# version_0_test.net
KiCad netlist of a schematic drawn in EAGLE
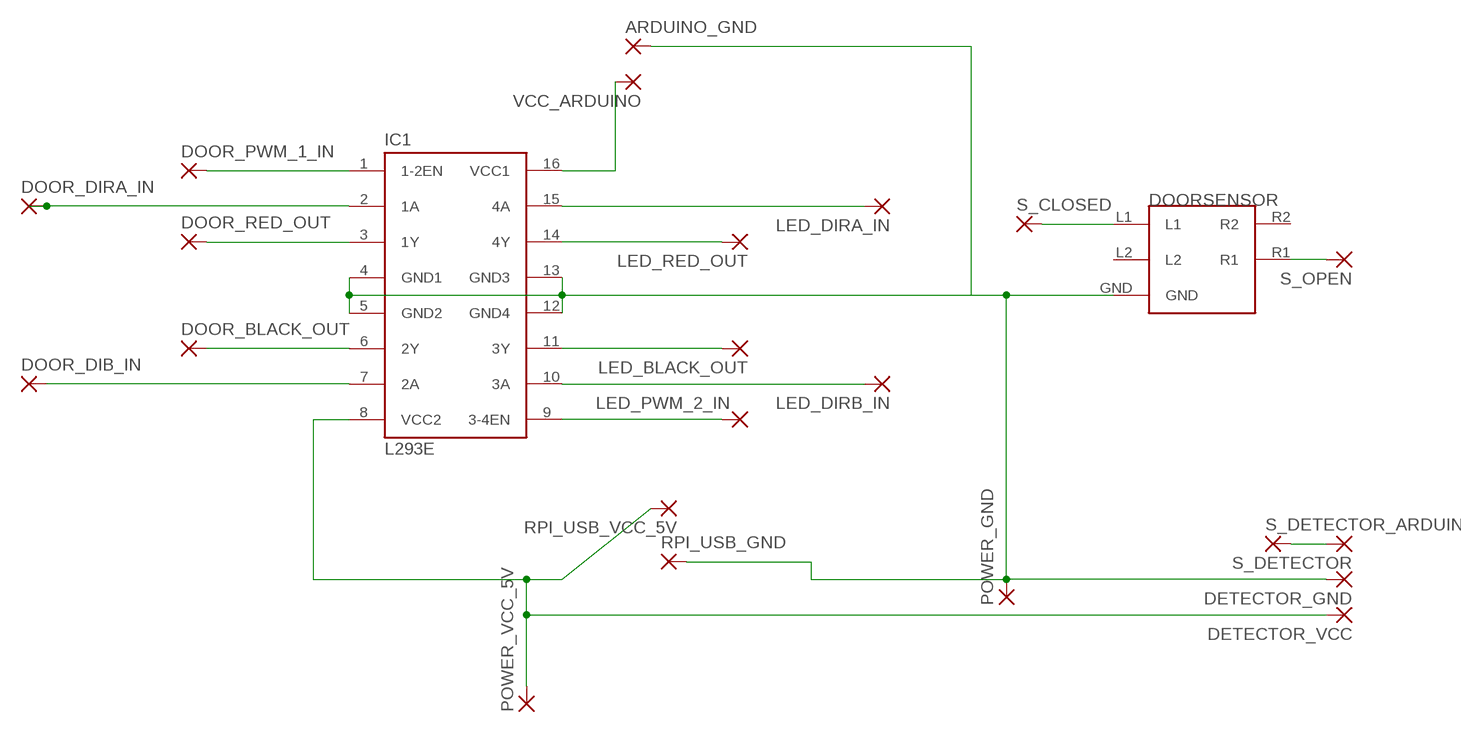
[diagram p0: schematic, sheet 1]

(export (version "E")
  (design (tool "Eeschema 10.0.6"))
  (components
    (comp (ref "ARDUINO_GND")
      (value "SMD5")
      (footprint "eagle-import:SMD2,54-5,08")
      (libsource (lib "eagle-import") (part "SMD5"))
    )
    (comp (ref "DETECTOR_GND")
      (value "SMD5")
      (footprint "eagle-import:SMD2,54-5,08")
      (libsource (lib "eagle-import") (part "SMD5"))
    )
    (comp (ref "DETECTOR_VCC")
      (value "SMD5")
      (footprint "eagle-import:SMD2,54-5,08")
      (libsource (lib "eagle-import") (part "SMD5"))
    )
    (comp (ref "DOORSENSOR")
      (value "DOORSENSOR")
      (footprint "eagle-import:DOORSENSOR")
      (libsource (lib "eagle-import") (part "DOORSENSOR"))
    )
    (comp (ref "DOOR_BLACK_OUT")
      (value "SMD5")
      (footprint "eagle-import:SMD2,54-5,08")
      (libsource (lib "eagle-import") (part "SMD5"))
    )
    (comp (ref "DOOR_DIB_IN")
      (value "SMD5")
      (footprint "eagle-import:SMD2,54-5,08")
      (libsource (lib "eagle-import") (part "SMD5"))
    )
    (comp (ref "DOOR_DIRA_IN")
      (value "SMD5")
      (footprint "eagle-import:SMD2,54-5,08")
      (libsource (lib "eagle-import") (part "SMD5"))
    )
    (comp (ref "DOOR_PWM_1_IN")
      (value "SMD5")
      (footprint "eagle-import:SMD2,54-5,08")
      (libsource (lib "eagle-import") (part "SMD5"))
    )
    (comp (ref "DOOR_RED_OUT")
      (value "SMD5")
      (footprint "eagle-import:SMD2,54-5,08")
      (libsource (lib "eagle-import") (part "SMD5"))
    )
    (comp (ref "IC1")
      (value "L293E")
      (footprint "eagle-import:DIL16")
      (fields (field (name "MF") "Arrow Electronics"))
      (libsource (lib "eagle-import") (part "L293E"))
    )
    (comp (ref "LED_BLACK_OUT")
      (value "SMD5")
      (footprint "eagle-import:SMD2,54-5,08")
      (libsource (lib "eagle-import") (part "SMD5"))
    )
    (comp (ref "LED_DIRA_IN")
      (value "SMD5")
      (footprint "eagle-import:SMD2,54-5,08")
      (libsource (lib "eagle-import") (part "SMD5"))
    )
    (comp (ref "LED_DIRB_IN")
      (value "SMD5")
      (footprint "eagle-import:SMD2,54-5,08")
      (libsource (lib "eagle-import") (part "SMD5"))
    )
    (comp (ref "LED_PWM_2_IN")
      (value "SMD5")
      (footprint "eagle-import:SMD2,54-5,08")
      (libsource (lib "eagle-import") (part "SMD5"))
    )
    (comp (ref "LED_RED_OUT")
      (value "SMD5")
      (footprint "eagle-import:SMD2,54-5,08")
      (libsource (lib "eagle-import") (part "SMD5"))
    )
    (comp (ref "POWER_GND")
      (value "SMD5")
      (footprint "eagle-import:SMD2,54-5,08")
      (libsource (lib "eagle-import") (part "SMD5"))
    )
    (comp (ref "POWER_VCC_5V")
      (value "SMD5")
      (footprint "eagle-import:SMD2,54-5,08")
      (libsource (lib "eagle-import") (part "SMD5"))
    )
    (comp (ref "RPI_USB_GND")
      (value "SMD5")
      (footprint "eagle-import:SMD2,54-5,08")
      (libsource (lib "eagle-import") (part "SMD5"))
    )
    (comp (ref "RPI_USB_VCC_5V")
      (value "SMD5")
      (footprint "eagle-import:SMD2,54-5,08")
      (libsource (lib "eagle-import") (part "SMD5"))
    )
    (comp (ref "S_CLOSED")
      (value "SMD5")
      (footprint "eagle-import:SMD2,54-5,08")
      (libsource (lib "eagle-import") (part "SMD5"))
    )
    (comp (ref "S_DETECTOR")
      (value "SMD5")
      (footprint "eagle-import:SMD2,54-5,08")
      (libsource (lib "eagle-import") (part "SMD5"))
    )
    (comp (ref "S_DETECTOR_ARDUINO")
      (value "SMD5")
      (footprint "eagle-import:SMD2,54-5,08")
      (libsource (lib "eagle-import") (part "SMD5"))
    )
    (comp (ref "S_OPEN")
      (value "SMD5")
      (footprint "eagle-import:SMD2,54-5,08")
      (libsource (lib "eagle-import") (part "SMD5"))
    )
    (comp (ref "VCC_ARDUINO")
      (value "SMD5")
      (footprint "eagle-import:SMD2,54-5,08")
      (libsource (lib "eagle-import") (part "SMD5"))
    )
  )
  (nets
    (net (code "1") (name "Net-(ARDUINO_GND-P)") (class "Default")
      (node (ref "ARDUINO_GND") (pin "1") (pinfunction "P_1") (pintype "passive"))
      (node (ref "DETECTOR_GND") (pin "1") (pinfunction "P_1") (pintype "passive"))
      (node (ref "DOORSENSOR") (pin "GND") (pinfunction "GND_GND") (pintype "bidirectional"))
      (node (ref "IC1") (pin "12") (pinfunction "GND4_12") (pintype "power_in"))
      (node (ref "IC1") (pin "13") (pinfunction "GND3_13") (pintype "power_in"))
      (node (ref "IC1") (pin "4") (pinfunction "GND1_4") (pintype "power_in"))
      (node (ref "IC1") (pin "5") (pinfunction "GND2_5") (pintype "power_in"))
      (node (ref "POWER_GND") (pin "1") (pinfunction "P_1") (pintype "passive"))
      (node (ref "RPI_USB_GND") (pin "1") (pinfunction "P_1") (pintype "passive"))
    )
    (net (code "2") (name "Net-(DETECTOR_VCC-P)") (class "Default")
      (node (ref "DETECTOR_VCC") (pin "1") (pinfunction "P_1") (pintype "passive"))
      (node (ref "IC1") (pin "8") (pinfunction "VCC2_8") (pintype "power_in"))
      (node (ref "POWER_VCC_5V") (pin "1") (pinfunction "P_1") (pintype "passive"))
      (node (ref "RPI_USB_VCC_5V") (pin "1") (pinfunction "P_1") (pintype "passive"))
    )
    (net (code "3") (name "Net-(DOOR_BLACK_OUT-P)") (class "Default")
      (node (ref "DOOR_BLACK_OUT") (pin "1") (pinfunction "P_1") (pintype "passive"))
      (node (ref "IC1") (pin "6") (pinfunction "2Y_6") (pintype "output"))
    )
    (net (code "4") (name "Net-(DOOR_DIB_IN-P)") (class "Default")
      (node (ref "DOOR_DIB_IN") (pin "1") (pinfunction "P_1") (pintype "passive"))
      (node (ref "IC1") (pin "7") (pinfunction "2A_7") (pintype "input"))
    )
    (net (code "5") (name "Net-(DOOR_DIRA_IN-P)") (class "Default")
      (node (ref "DOOR_DIRA_IN") (pin "1") (pinfunction "P_1") (pintype "passive"))
      (node (ref "IC1") (pin "2") (pinfunction "1A_2") (pintype "input"))
    )
    (net (code "6") (name "Net-(DOOR_PWM_1_IN-P)") (class "Default")
      (node (ref "DOOR_PWM_1_IN") (pin "1") (pinfunction "P_1") (pintype "passive"))
      (node (ref "IC1") (pin "1") (pinfunction "1-2EN_1") (pintype "input"))
    )
    (net (code "7") (name "Net-(DOOR_RED_OUT-P)") (class "Default")
      (node (ref "DOOR_RED_OUT") (pin "1") (pinfunction "P_1") (pintype "passive"))
      (node (ref "IC1") (pin "3") (pinfunction "1Y_3") (pintype "output"))
    )
    (net (code "8") (name "Net-(IC1-3-4EN)") (class "Default")
      (node (ref "IC1") (pin "9") (pinfunction "3-4EN_9") (pintype "input"))
      (node (ref "LED_PWM_2_IN") (pin "1") (pinfunction "P_1") (pintype "passive"))
    )
    (net (code "9") (name "Net-(IC1-3A)") (class "Default")
      (node (ref "IC1") (pin "10") (pinfunction "3A_10") (pintype "input"))
      (node (ref "LED_DIRB_IN") (pin "1") (pinfunction "P_1") (pintype "passive"))
    )
    (net (code "10") (name "Net-(IC1-3Y)") (class "Default")
      (node (ref "IC1") (pin "11") (pinfunction "3Y_11") (pintype "output"))
      (node (ref "LED_BLACK_OUT") (pin "1") (pinfunction "P_1") (pintype "passive"))
    )
    (net (code "11") (name "Net-(IC1-4A)") (class "Default")
      (node (ref "IC1") (pin "15") (pinfunction "4A_15") (pintype "input"))
      (node (ref "LED_DIRA_IN") (pin "1") (pinfunction "P_1") (pintype "passive"))
    )
    (net (code "12") (name "Net-(IC1-4Y)") (class "Default")
      (node (ref "IC1") (pin "14") (pinfunction "4Y_14") (pintype "output"))
      (node (ref "LED_RED_OUT") (pin "1") (pinfunction "P_1") (pintype "passive"))
    )
    (net (code "13") (name "Net-(IC1-VCC1)") (class "Default")
      (node (ref "IC1") (pin "16") (pinfunction "VCC1_16") (pintype "power_in"))
      (node (ref "VCC_ARDUINO") (pin "1") (pinfunction "P_1") (pintype "passive"))
    )
    (net (code "14") (name "Net-(S_CLOSED-P)") (class "Default")
      (node (ref "DOORSENSOR") (pin "L1") (pinfunction "L1_L1") (pintype "bidirectional"))
      (node (ref "S_CLOSED") (pin "1") (pinfunction "P_1") (pintype "passive"))
    )
    (net (code "15") (name "Net-(S_DETECTOR-P)") (class "Default")
      (node (ref "S_DETECTOR") (pin "1") (pinfunction "P_1") (pintype "passive"))
      (node (ref "S_DETECTOR_ARDUINO") (pin "1") (pinfunction "P_1") (pintype "passive"))
    )
    (net (code "16") (name "Net-(S_OPEN-P)") (class "Default")
      (node (ref "DOORSENSOR") (pin "R1") (pinfunction "R1_R1") (pintype "bidirectional"))
      (node (ref "S_OPEN") (pin "1") (pinfunction "P_1") (pintype "passive"))
    )
    (net (code "17") (name "unconnected-(DOORSENSOR-PadL2)") (class "Default")
      (node (ref "DOORSENSOR") (pin "L2") (pinfunction "L2_L2") (pintype "bidirectional"))
    )
    (net (code "18") (name "unconnected-(DOORSENSOR-PadR2)") (class "Default")
      (node (ref "DOORSENSOR") (pin "R2") (pinfunction "R2_R2") (pintype "bidirectional"))
    )
  )
)
